# robot-basketball-basket-counter.net
KiCad netlist of a schematic drawn in Altium Designer
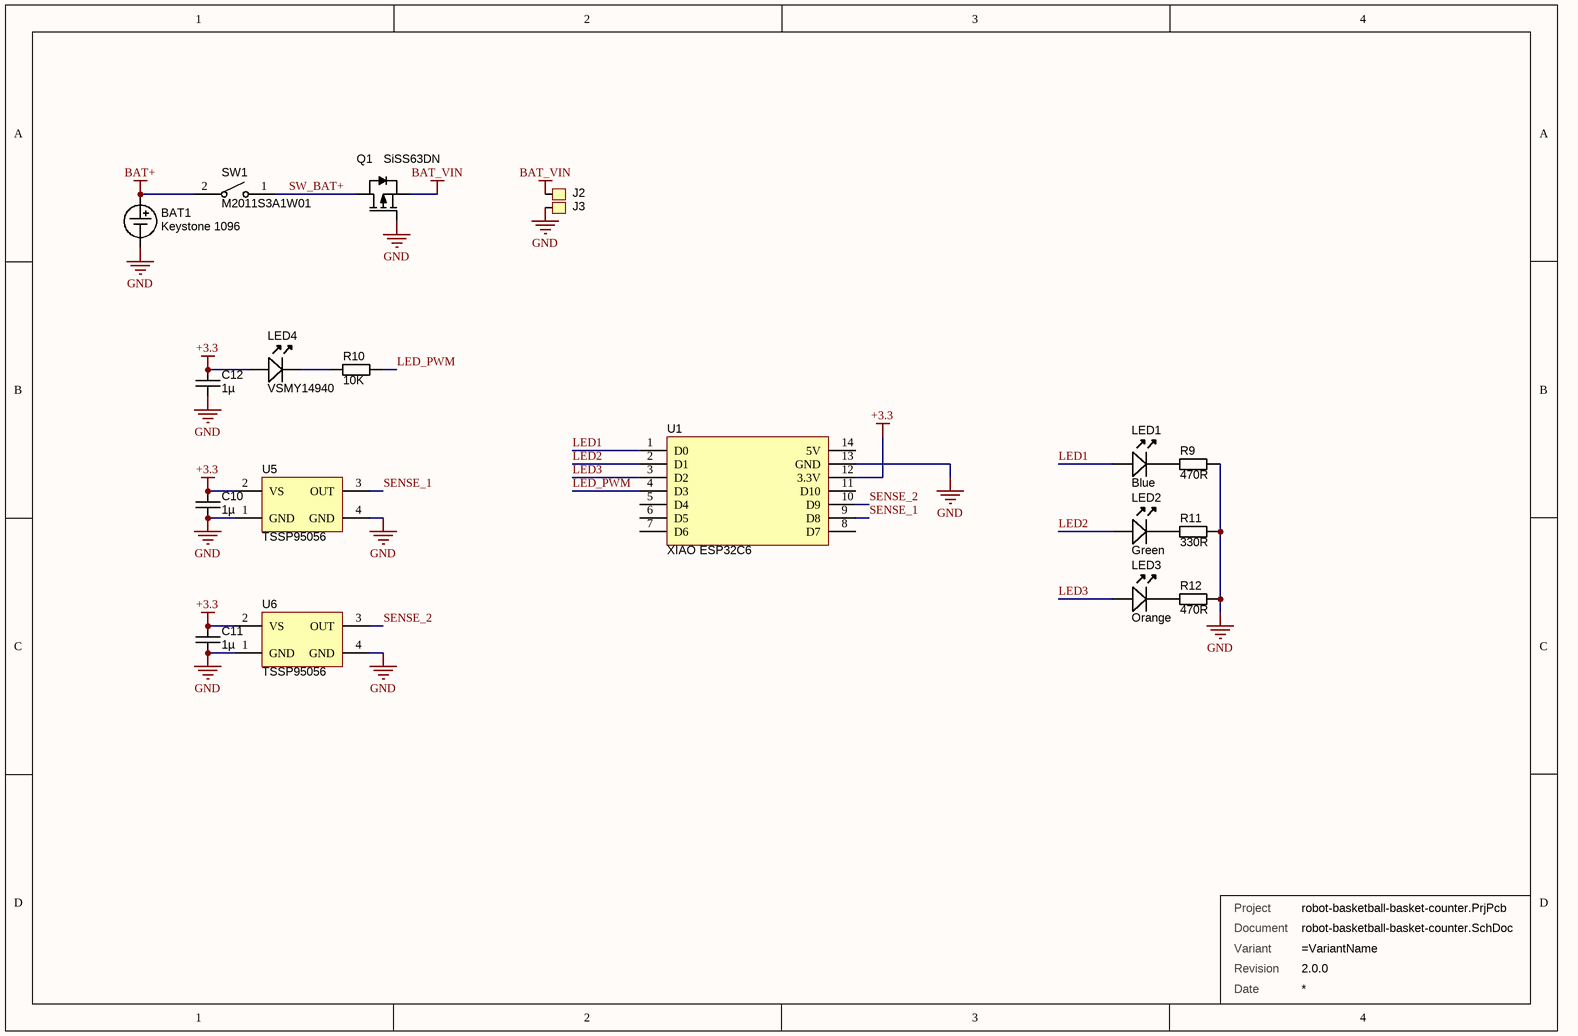
[diagram p0: robot-basketball-basket-counter.SchDoc]

(export (version "E")
  (design (tool "Eeschema 10.0.6"))
  (components
    (comp (ref "BAT1")
      (value "Keystone 1096")
      (footprint "Keystone_PN1096")
      (libsource (lib "robot-basketball-basket-counter") (part "Keystone_1096"))
    )
    (comp (ref "C10")
      (value "1µ")
      (footprint "CAPC1608X90N")
      (description "Capacitor SMD Cer 1uF 10% 16V X7R 0603")
      (fields (field (name "TOLERANCE") "±10%") (field (name "Comment") "approved sub OK"))
      (libsource (lib "PBL - Capacitors") (part "CAPC_1u_0603_X7R_16V_10%"))
    )
    (comp (ref "C11")
      (value "1µ")
      (footprint "CAPC1608X90N")
      (description "Capacitor SMD Cer 1uF 10% 16V X7R 0603")
      (fields (field (name "TOLERANCE") "±10%") (field (name "Comment") "approved sub OK"))
      (libsource (lib "PBL - Capacitors") (part "CAPC_1u_0603_X7R_16V_10%"))
    )
    (comp (ref "C12")
      (value "1µ")
      (footprint "CAPC1608X90N")
      (description "Capacitor SMD Cer 1uF 10% 16V X7R 0603")
      (fields (field (name "TOLERANCE") "±10%") (field (name "Comment") "approved sub OK"))
      (libsource (lib "PBL - Capacitors") (part "CAPC_1u_0603_X7R_16V_10%"))
    )
    (comp (ref "J2")
      (value "PAD")
      (footprint "PAD_3.0x2.0")
      (libsource (lib "robot-basketball-basket-counter") (part "PAD"))
    )
    (comp (ref "J3")
      (value "PAD")
      (footprint "PAD_3.0x2.0")
      (libsource (lib "robot-basketball-basket-counter") (part "PAD"))
    )
    (comp (ref "LED1")
      (value "Blue")
      (footprint "LED-0603-GREEN")
      (description "LED 0603 SMD Green 570nm 50mcd 20mA")
      (libsource (lib "PBL - Light Sources") (part "LED_SMD_Green_0603_570nm"))
    )
    (comp (ref "LED2")
      (value "Green")
      (footprint "LED-0603-GREEN")
      (description "LED 0603 SMD Green 570nm 50mcd 20mA")
      (libsource (lib "PBL - Light Sources") (part "LED_SMD_Green_0603_570nm"))
    )
    (comp (ref "LED3")
      (value "Orange")
      (footprint "LED-0603-YELLOW")
      (description "LED 0603 SMD Yellow 590nm 150mcd 20mA")
      (libsource (lib "PBL - Light Sources") (part "LED_SMD_Yellow_0603_150mcd"))
    )
    (comp (ref "LED4")
      (value "VSMY14940")
      (footprint "VSMY14940")
      (libsource (lib "robot-basketball-basket-counter") (part "VSMY14940"))
    )
    (comp (ref "Q1")
      (value "SiSS63DN")
      (footprint "Vishay_PowerPAK_1212-8S")
      (libsource (lib "robot-basketball-basket-counter") (part "SiSS63DN"))
    )
    (comp (ref "R9")
      (value "470R")
      (footprint "RESC1608X55N")
      (description "Resistor SMD chip 470 Ohm 0.1W 5% 0603")
      (fields (field (name "TOLERANCE") "±5%") (field (name "Comment") "Thick Film"))
      (libsource (lib "PBL - Resistors") (part "RES_470R_0603_5%"))
    )
    (comp (ref "R10")
      (value "10K")
      (footprint "RESC1608X55N")
      (description "Resistor SMD chip 10k Ohm 0.1W 1% 0603")
      (fields (field (name "TOLERANCE") "±1%") (field (name "Comment") "Thick Film"))
      (libsource (lib "PBL - Resistors") (part "RES_10K_0603_1%"))
    )
    (comp (ref "R11")
      (value "330R")
      (footprint "RESC1608X55N")
      (description "Resistor SMD chip 330 Ohm 0.1W 5% 0603")
      (fields (field (name "TOLERANCE") "±5%") (field (name "Comment") "Thick Film"))
      (libsource (lib "PBL - Resistors") (part "RES_330R_0603_5%"))
    )
    (comp (ref "R12")
      (value "470R")
      (footprint "RESC1608X55N")
      (description "Resistor SMD chip 470 Ohm 0.1W 5% 0603")
      (fields (field (name "TOLERANCE") "±5%") (field (name "Comment") "Thick Film"))
      (libsource (lib "PBL - Resistors") (part "RES_470R_0603_5%"))
    )
    (comp (ref "SW1")
      (value "M2011S3A1W01")
      (footprint "M2011S3A1W01")
      (libsource (lib "robot-basketball-basket-counter") (part "M2011S3A1W01"))
    )
    (comp (ref "TitleBlock")
      (value "TitleBlock")
      (libsource (lib "robot-basketball-basket-counter") (part "TitleBlock"))
    )
    (comp (ref "U1")
      (value "XIAO ESP32C6")
      (footprint "XIAO_ESP32_C6")
      (libsource (lib "robot-basketball-basket-counter") (part "XIAO_ESP32_C6"))
    )
    (comp (ref "U5")
      (value "TSSP95056")
      (footprint "VISHAY_HEIMDALL_VERTICAL")
      (libsource (lib "robot-basketball-basket-counter") (part "TSSP95056"))
    )
    (comp (ref "U6")
      (value "TSSP95056")
      (footprint "VISHAY_HEIMDALL_VERTICAL")
      (libsource (lib "robot-basketball-basket-counter") (part "TSSP95056"))
    )
  )
  (nets
    (net (code "1") (name "+3.3") (class "Default")
      (node (ref "C10") (pin "1") (pintype "passive"))
      (node (ref "C11") (pin "1") (pintype "passive"))
      (node (ref "C12") (pin "1") (pintype "passive"))
      (node (ref "LED4") (pin "A") (pinfunction "A_A") (pintype "passive"))
      (node (ref "U1") (pin "12") (pinfunction "3.3V_12") (pintype "passive"))
      (node (ref "U5") (pin "2") (pinfunction "VS_2") (pintype "passive"))
      (node (ref "U6") (pin "2") (pinfunction "VS_2") (pintype "passive"))
    )
    (net (code "2") (name "/LED1") (class "Default")
      (node (ref "LED1") (pin "A") (pinfunction "A_A") (pintype "passive"))
      (node (ref "U1") (pin "1") (pinfunction "D0_1") (pintype "passive"))
    )
    (net (code "3") (name "/LED2") (class "Default")
      (node (ref "LED2") (pin "A") (pinfunction "A_A") (pintype "passive"))
      (node (ref "U1") (pin "2") (pinfunction "D1_2") (pintype "passive"))
    )
    (net (code "4") (name "/LED3") (class "Default")
      (node (ref "LED3") (pin "A") (pinfunction "A_A") (pintype "passive"))
      (node (ref "U1") (pin "3") (pinfunction "D2_3") (pintype "passive"))
    )
    (net (code "5") (name "/LED_PWM") (class "Default")
      (node (ref "R10") (pin "1") (pinfunction "1_1") (pintype "passive"))
      (node (ref "U1") (pin "4") (pinfunction "D3_4") (pintype "passive"))
    )
    (net (code "6") (name "/SENSE_1") (class "Default")
      (node (ref "U1") (pin "9") (pinfunction "D8_9") (pintype "passive"))
      (node (ref "U5") (pin "3") (pinfunction "OUT_3") (pintype "passive"))
    )
    (net (code "7") (name "/SENSE_2") (class "Default")
      (node (ref "U1") (pin "10") (pinfunction "D9_10") (pintype "passive"))
      (node (ref "U6") (pin "3") (pinfunction "OUT_3") (pintype "passive"))
    )
    (net (code "8") (name "/SW_BAT+") (class "Default")
      (node (ref "Q1") (pin "D") (pinfunction "D_D") (pintype "passive"))
      (node (ref "SW1") (pin "1") (pinfunction "1_1") (pintype "passive"))
    )
    (net (code "9") (name "BAT+") (class "Default")
      (node (ref "BAT1") (pin "plus") (pinfunction "plus_plus") (pintype "passive"))
      (node (ref "SW1") (pin "2") (pinfunction "2_2") (pintype "passive"))
    )
    (net (code "10") (name "BAT_VIN") (class "Default")
      (node (ref "J2") (pin "1") (pinfunction "1_1") (pintype "passive"))
      (node (ref "Q1") (pin "S") (pinfunction "S_S") (pintype "passive"))
    )
    (net (code "11") (name "GND") (class "Default")
      (node (ref "BAT1") (pin "minus") (pinfunction "minus_minus") (pintype "passive"))
      (node (ref "C10") (pin "2") (pintype "passive"))
      (node (ref "C11") (pin "2") (pintype "passive"))
      (node (ref "C12") (pin "2") (pintype "passive"))
      (node (ref "J3") (pin "1") (pinfunction "1_1") (pintype "passive"))
      (node (ref "Q1") (pin "G") (pinfunction "G_G") (pintype "passive"))
      (node (ref "R11") (pin "1") (pinfunction "1_1") (pintype "passive"))
      (node (ref "R12") (pin "1") (pinfunction "1_1") (pintype "passive"))
      (node (ref "R9") (pin "1") (pinfunction "1_1") (pintype "passive"))
      (node (ref "U1") (pin "13") (pinfunction "GND_13") (pintype "passive"))
      (node (ref "U5") (pin "1") (pinfunction "GND_1") (pintype "passive"))
      (node (ref "U5") (pin "4") (pinfunction "GND_4") (pintype "passive"))
      (node (ref "U6") (pin "1") (pinfunction "GND_1") (pintype "passive"))
      (node (ref "U6") (pin "4") (pinfunction "GND_4") (pintype "passive"))
    )
    (net (code "12") (name "Net-(LED1-PadK)") (class "Default")
      (node (ref "LED1") (pin "K") (pinfunction "K_K") (pintype "passive"))
      (node (ref "R9") (pin "2") (pinfunction "2_2") (pintype "passive"))
    )
    (net (code "13") (name "Net-(LED2-PadK)") (class "Default")
      (node (ref "LED2") (pin "K") (pinfunction "K_K") (pintype "passive"))
      (node (ref "R11") (pin "2") (pinfunction "2_2") (pintype "passive"))
    )
    (net (code "14") (name "Net-(LED3-PadK)") (class "Default")
      (node (ref "LED3") (pin "K") (pinfunction "K_K") (pintype "passive"))
      (node (ref "R12") (pin "2") (pinfunction "2_2") (pintype "passive"))
    )
    (net (code "15") (name "Net-(LED4-PadK)") (class "Default")
      (node (ref "LED4") (pin "K") (pinfunction "K_K") (pintype "passive"))
      (node (ref "R10") (pin "2") (pinfunction "2_2") (pintype "passive"))
    )
    (net (code "16") (name "unconnected-(U1-5V-Pad14)") (class "Default")
      (node (ref "U1") (pin "14") (pinfunction "5V_14") (pintype "passive"))
    )
    (net (code "17") (name "unconnected-(U1-D4-Pad5)") (class "Default")
      (node (ref "U1") (pin "5") (pinfunction "D4_5") (pintype "passive"))
    )
    (net (code "18") (name "unconnected-(U1-D5-Pad6)") (class "Default")
      (node (ref "U1") (pin "6") (pinfunction "D5_6") (pintype "passive"))
    )
    (net (code "19") (name "unconnected-(U1-D6-Pad7)") (class "Default")
      (node (ref "U1") (pin "7") (pinfunction "D6_7") (pintype "passive"))
    )
    (net (code "20") (name "unconnected-(U1-D7-Pad8)") (class "Default")
      (node (ref "U1") (pin "8") (pinfunction "D7_8") (pintype "passive"))
    )
    (net (code "21") (name "unconnected-(U1-D10-Pad11)") (class "Default")
      (node (ref "U1") (pin "11") (pinfunction "D10_11") (pintype "passive"))
    )
  )
)
